# Adafruit_QT_Py_RP2040.net
KiCad netlist of a schematic drawn in EAGLE
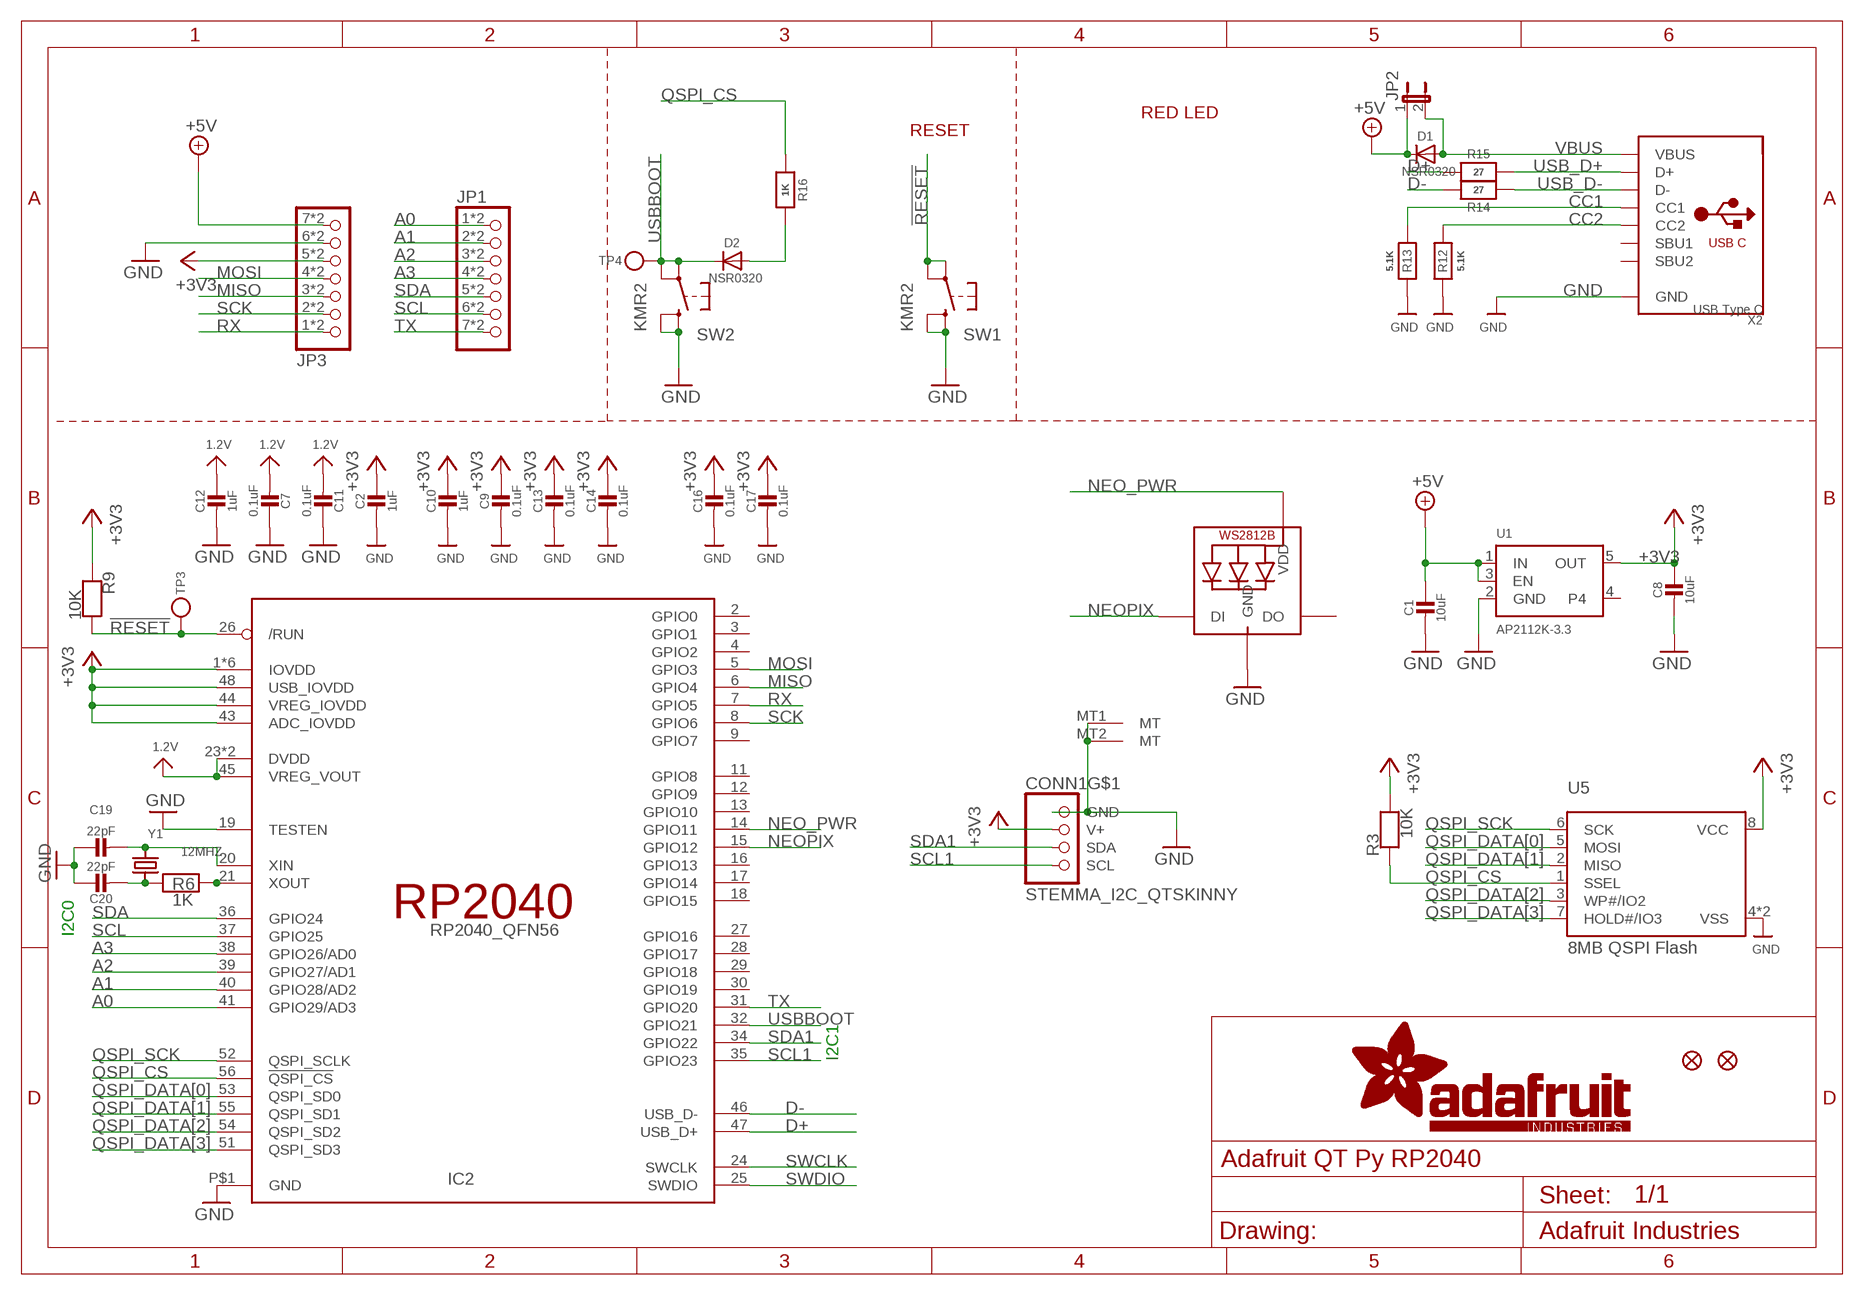
[diagram p0: schematic, sheet 1]

(export (version "E")
  (design (tool "Eeschema 10.0.6"))
  (components
    (comp (ref "C1")
      (value "10uF")
      (footprint "eagle-import:0805-NO")
      (libsource (lib "eagle-import") (part "CAP_CERAMIC0805-NOOUTLINE"))
    )
    (comp (ref "C2")
      (value "1uF")
      (footprint "eagle-import:0603-NO")
      (libsource (lib "eagle-import") (part "CAP_CERAMIC0603_NO"))
    )
    (comp (ref "C7")
      (value "0.1uF")
      (footprint "eagle-import:_0402NO")
      (libsource (lib "eagle-import") (part "CAP_CERAMIC_0402NO"))
    )
    (comp (ref "C8")
      (value "10uF")
      (footprint "eagle-import:0805-NO")
      (libsource (lib "eagle-import") (part "CAP_CERAMIC0805-NOOUTLINE"))
    )
    (comp (ref "C9")
      (value "0.1uF")
      (footprint "eagle-import:_0402NO")
      (libsource (lib "eagle-import") (part "CAP_CERAMIC_0402NO"))
    )
    (comp (ref "C10")
      (value "1uF")
      (footprint "eagle-import:0603-NO")
      (libsource (lib "eagle-import") (part "CAP_CERAMIC0603_NO"))
    )
    (comp (ref "C11")
      (value "0.1uF")
      (footprint "eagle-import:_0402NO")
      (libsource (lib "eagle-import") (part "CAP_CERAMIC_0402NO"))
    )
    (comp (ref "C12")
      (value "1uF")
      (footprint "eagle-import:0603-NO")
      (libsource (lib "eagle-import") (part "CAP_CERAMIC0603_NO"))
    )
    (comp (ref "C13")
      (value "0.1uF")
      (footprint "eagle-import:_0402NO")
      (libsource (lib "eagle-import") (part "CAP_CERAMIC_0402NO"))
    )
    (comp (ref "C14")
      (value "0.1uF")
      (footprint "eagle-import:_0402NO")
      (libsource (lib "eagle-import") (part "CAP_CERAMIC_0402NO"))
    )
    (comp (ref "C16")
      (value "0.1uF")
      (footprint "eagle-import:_0402NO")
      (libsource (lib "eagle-import") (part "CAP_CERAMIC_0402NO"))
    )
    (comp (ref "C17")
      (value "0.1uF")
      (footprint "eagle-import:_0402NO")
      (libsource (lib "eagle-import") (part "CAP_CERAMIC_0402NO"))
    )
    (comp (ref "C19")
      (value "22pF")
      (footprint "eagle-import:_0402NO")
      (libsource (lib "eagle-import") (part "CAP_CERAMIC_0402NO"))
    )
    (comp (ref "C20")
      (value "22pF")
      (footprint "eagle-import:_0402NO")
      (libsource (lib "eagle-import") (part "CAP_CERAMIC_0402NO"))
    )
    (comp (ref "CONN1")
      (value "STEMMA_I2C_QTSKINNY")
      (footprint "eagle-import:JST_SH4_SKINNY")
      (libsource (lib "eagle-import") (part "STEMMA_I2C_QTSKINNY"))
    )
    (comp (ref "D1")
      (value "NSR0320")
      (footprint "eagle-import:SOD-323_MINI")
      (libsource (lib "eagle-import") (part "DIODE_SOD323MINI"))
    )
    (comp (ref "D2")
      (value "NSR0320")
      (footprint "eagle-import:SOD-323_MINI")
      (libsource (lib "eagle-import") (part "DIODE_SOD323MINI"))
    )
    (comp (ref "IC2")
      (value "RP2040_QFN56")
      (footprint "eagle-import:QFN56_7MM_REDUCEDEPAD")
      (libsource (lib "eagle-import") (part "RP2040_QFN56"))
    )
    (comp (ref "JP1")
      (value "HEADER-1X7_CASTEL")
      (footprint "eagle-import:1X07_CASTEL")
      (libsource (lib "eagle-import") (part "HEADER-1X7_CASTEL"))
    )
    (comp (ref "JP2")
      (value "JUMPER-2SMD-NO")
      (footprint "eagle-import:SJ_2S-NO")
      (libsource (lib "eagle-import") (part "JUMPER-2SMD-NO"))
    )
    (comp (ref "JP3")
      (value "HEADER-1X7_CASTEL")
      (footprint "eagle-import:1X07_CASTEL")
      (libsource (lib "eagle-import") (part "HEADER-1X7_CASTEL"))
    )
    (comp (ref "LED1")
      (value "WS2812B_SK6805_1515")
      (footprint "eagle-import:SK6805_1515")
      (libsource (lib "eagle-import") (part "WS2812B_SK6805_1515"))
    )
    (comp (ref "R3")
      (value "10K")
      (footprint "eagle-import:_0402NO")
      (libsource (lib "eagle-import") (part "RESISTOR_0402NO"))
    )
    (comp (ref "R6")
      (value "1K")
      (footprint "eagle-import:_0402NO")
      (libsource (lib "eagle-import") (part "RESISTOR_0402NO"))
    )
    (comp (ref "R9")
      (value "10K")
      (footprint "eagle-import:_0402NO")
      (libsource (lib "eagle-import") (part "RESISTOR_0402NO"))
    )
    (comp (ref "R12")
      (value "5.1K")
      (footprint "eagle-import:_0402NO")
      (libsource (lib "eagle-import") (part "RESISTOR_0402NO"))
    )
    (comp (ref "R13")
      (value "5.1K")
      (footprint "eagle-import:_0402NO")
      (libsource (lib "eagle-import") (part "RESISTOR_0402NO"))
    )
    (comp (ref "R14")
      (value "27")
      (footprint "eagle-import:_0402NO")
      (libsource (lib "eagle-import") (part "RESISTOR_0402NO"))
    )
    (comp (ref "R15")
      (value "27")
      (footprint "eagle-import:_0402NO")
      (libsource (lib "eagle-import") (part "RESISTOR_0402NO"))
    )
    (comp (ref "R16")
      (value "1K")
      (footprint "eagle-import:_0402NO")
      (libsource (lib "eagle-import") (part "RESISTOR_0402NO"))
    )
    (comp (ref "SW1")
      (value "KMR2")
      (footprint "eagle-import:BTN_KMR2_4.6X2.8")
      (libsource (lib "eagle-import") (part "SWITCH_TACT_SMT4.6X2.8"))
    )
    (comp (ref "SW2")
      (value "KMR2")
      (footprint "eagle-import:BTN_KMR2_4.6X2.8")
      (libsource (lib "eagle-import") (part "SWITCH_TACT_SMT4.6X2.8"))
    )
    (comp (ref "TP3")
      (value "TESTPOINTROUND1.5MMNO")
      (footprint "eagle-import:TESTPOINT_ROUND_1.5MM_NO")
      (libsource (lib "eagle-import") (part "TESTPOINTROUND1.5MMNO"))
    )
    (comp (ref "TP4")
      (value "TESTPOINTROUND1.5MMNO")
      (footprint "eagle-import:TESTPOINT_ROUND_1.5MM_NO")
      (libsource (lib "eagle-import") (part "TESTPOINTROUND1.5MMNO"))
    )
    (comp (ref "U$6")
      (value "FIDUCIAL_1MM")
      (footprint "eagle-import:FIDUCIAL_1MM")
      (libsource (lib "eagle-import") (part "FIDUCIAL_1MM"))
    )
    (comp (ref "U$8")
      (value "FIDUCIAL_1MM")
      (footprint "eagle-import:FIDUCIAL_1MM")
      (libsource (lib "eagle-import") (part "FIDUCIAL_1MM"))
    )
    (comp (ref "U1")
      (value "AP2112K-3.3")
      (footprint "eagle-import:SOT23-5")
      (libsource (lib "eagle-import") (part "VREG_SOT23-5"))
    )
    (comp (ref "U5")
      (value "8MB QSPI Flash")
      (footprint "eagle-import:USON8_4X4")
      (libsource (lib "eagle-import") (part "SPIFLASH_8PIN_4X4"))
    )
    (comp (ref "X2")
      (value "USB Type C")
      (footprint "eagle-import:USB_C_CUSB31-CFM2AX-01-X")
      (libsource (lib "eagle-import") (part "USB_C"))
    )
    (comp (ref "Y1")
      (value "12MHZ")
      (footprint "eagle-import:CRYSTAL_2.5X2")
      (libsource (lib "eagle-import") (part "CRYSTAL2.5X2.0"))
    )
  )
  (nets
    (net (code "1") (name "+3V3") (class "Default")
      (node (ref "C10") (pin "1") (pinfunction "1_1") (pintype "passive"))
      (node (ref "C13") (pin "1") (pinfunction "1_1") (pintype "passive"))
      (node (ref "C14") (pin "1") (pinfunction "1_1") (pintype "passive"))
      (node (ref "C16") (pin "1") (pinfunction "1_1") (pintype "passive"))
      (node (ref "C17") (pin "1") (pinfunction "1_1") (pintype "passive"))
      (node (ref "C2") (pin "1") (pinfunction "1_1") (pintype "passive"))
      (node (ref "C8") (pin "1") (pinfunction "1_1") (pintype "passive"))
      (node (ref "C9") (pin "1") (pinfunction "1_1") (pintype "passive"))
      (node (ref "CONN1") (pin "2") (pinfunction "V+_2") (pintype "passive"))
      (node (ref "IC2") (pin "1") (pinfunction "IOVDD_1") (pintype "power_in"))
      (node (ref "IC2") (pin "10") (pinfunction "IOVDD_10") (pintype "power_in"))
      (node (ref "IC2") (pin "22") (pinfunction "IOVDD_22") (pintype "power_in"))
      (node (ref "IC2") (pin "33") (pinfunction "IOVDD_33") (pintype "power_in"))
      (node (ref "IC2") (pin "42") (pinfunction "IOVDD_42") (pintype "power_in"))
      (node (ref "IC2") (pin "43") (pinfunction "ADC_IOVDD_43") (pintype "power_in"))
      (node (ref "IC2") (pin "44") (pinfunction "VREG_IOVDD_44") (pintype "power_in"))
      (node (ref "IC2") (pin "48") (pinfunction "USB_IOVDD_48") (pintype "power_in"))
      (node (ref "IC2") (pin "49") (pinfunction "IOVDD_49") (pintype "power_in"))
      (node (ref "JP3") (pin "5") (pinfunction "5_5") (pintype "passive"))
      (node (ref "JP3") (pin "5C") (pinfunction "5_5C") (pintype "passive"))
      (node (ref "R3") (pin "2") (pinfunction "2_2") (pintype "passive"))
      (node (ref "R9") (pin "1") (pinfunction "1_1") (pintype "passive"))
      (node (ref "U1") (pin "5") (pinfunction "OUT_5") (pintype "power_in"))
      (node (ref "U5") (pin "8") (pinfunction "VCC_8") (pintype "bidirectional"))
    )
    (net (code "2") (name "+5V") (class "Default")
      (node (ref "C1") (pin "1") (pinfunction "1_1") (pintype "passive"))
      (node (ref "D1") (pin "C") (pinfunction "C_C") (pintype "passive"))
      (node (ref "JP2") (pin "1") (pinfunction "1_1") (pintype "passive"))
      (node (ref "JP3") (pin "7") (pinfunction "7_7") (pintype "passive"))
      (node (ref "JP3") (pin "7C") (pinfunction "7_7C") (pintype "passive"))
      (node (ref "U1") (pin "1") (pinfunction "IN_1") (pintype "power_in"))
      (node (ref "U1") (pin "3") (pinfunction "EN_3") (pintype "input"))
    )
    (net (code "3") (name "/A0") (class "Default")
      (node (ref "IC2") (pin "41") (pinfunction "GPIO29/AD3_41") (pintype "bidirectional"))
      (node (ref "JP1") (pin "1") (pinfunction "1_1") (pintype "passive"))
      (node (ref "JP1") (pin "1C") (pinfunction "1_1C") (pintype "passive"))
    )
    (net (code "4") (name "/A1") (class "Default")
      (node (ref "IC2") (pin "40") (pinfunction "GPIO28/AD2_40") (pintype "bidirectional"))
      (node (ref "JP1") (pin "2") (pinfunction "2_2") (pintype "passive"))
      (node (ref "JP1") (pin "2C") (pinfunction "2_2C") (pintype "passive"))
    )
    (net (code "5") (name "/A2") (class "Default")
      (node (ref "IC2") (pin "39") (pinfunction "GPIO27/AD1_39") (pintype "bidirectional"))
      (node (ref "JP1") (pin "3") (pinfunction "3_3") (pintype "passive"))
      (node (ref "JP1") (pin "3C") (pinfunction "3_3C") (pintype "passive"))
    )
    (net (code "6") (name "/A3") (class "Default")
      (node (ref "IC2") (pin "38") (pinfunction "GPIO26/AD0_38") (pintype "bidirectional"))
      (node (ref "JP1") (pin "4") (pinfunction "4_4") (pintype "passive"))
      (node (ref "JP1") (pin "4C") (pinfunction "4_4C") (pintype "passive"))
    )
    (net (code "7") (name "/CC1") (class "Default")
      (node (ref "R13") (pin "2") (pinfunction "2_2") (pintype "passive"))
      (node (ref "X2") (pin "A5") (pinfunction "CC1_A5") (pintype "bidirectional"))
    )
    (net (code "8") (name "/CC2") (class "Default")
      (node (ref "R12") (pin "2") (pinfunction "2_2") (pintype "passive"))
      (node (ref "X2") (pin "B5") (pinfunction "CC2_B5") (pintype "bidirectional"))
    )
    (net (code "9") (name "/D+") (class "Default")
      (node (ref "IC2") (pin "47") (pinfunction "USB_D+_47") (pintype "bidirectional"))
      (node (ref "R15") (pin "2") (pinfunction "2_2") (pintype "passive"))
    )
    (net (code "10") (name "/D-") (class "Default")
      (node (ref "IC2") (pin "46") (pinfunction "USB_D-_46") (pintype "bidirectional"))
      (node (ref "R14") (pin "2") (pinfunction "2_2") (pintype "passive"))
    )
    (net (code "11") (name "/MISO") (class "Default")
      (node (ref "IC2") (pin "6") (pinfunction "GPIO4_6") (pintype "bidirectional"))
      (node (ref "JP3") (pin "3") (pinfunction "3_3") (pintype "passive"))
      (node (ref "JP3") (pin "3C") (pinfunction "3_3C") (pintype "passive"))
    )
    (net (code "12") (name "/MOSI") (class "Default")
      (node (ref "IC2") (pin "5") (pinfunction "GPIO3_5") (pintype "bidirectional"))
      (node (ref "JP3") (pin "4") (pinfunction "4_4") (pintype "passive"))
      (node (ref "JP3") (pin "4C") (pinfunction "4_4C") (pintype "passive"))
    )
    (net (code "13") (name "/NEOPIX") (class "Default")
      (node (ref "IC2") (pin "15") (pinfunction "GPIO12_15") (pintype "bidirectional"))
      (node (ref "LED1") (pin "1") (pinfunction "DI_1") (pintype "input"))
    )
    (net (code "14") (name "/NEO_PWR") (class "Default")
      (node (ref "IC2") (pin "14") (pinfunction "GPIO11_14") (pintype "bidirectional"))
      (node (ref "LED1") (pin "2") (pinfunction "VDD_2") (pintype "power_in"))
    )
    (net (code "15") (name "/QSPI_CS") (class "Default")
      (node (ref "IC2") (pin "56") (pinfunction "~{QSPI_CS}_56") (pintype "bidirectional"))
      (node (ref "R16") (pin "1") (pinfunction "1_1") (pintype "passive"))
      (node (ref "R3") (pin "1") (pinfunction "1_1") (pintype "passive"))
      (node (ref "U5") (pin "1") (pinfunction "SSEL_1") (pintype "bidirectional"))
    )
    (net (code "16") (name "/QSPI_DATA[0]") (class "Default")
      (node (ref "IC2") (pin "53") (pinfunction "QSPI_SD0_53") (pintype "bidirectional"))
      (node (ref "U5") (pin "5") (pinfunction "MOSI_5") (pintype "bidirectional"))
    )
    (net (code "17") (name "/QSPI_DATA[1]") (class "Default")
      (node (ref "IC2") (pin "55") (pinfunction "QSPI_SD1_55") (pintype "bidirectional"))
      (node (ref "U5") (pin "2") (pinfunction "MISO_2") (pintype "bidirectional"))
    )
    (net (code "18") (name "/QSPI_DATA[2]") (class "Default")
      (node (ref "IC2") (pin "54") (pinfunction "QSPI_SD2_54") (pintype "bidirectional"))
      (node (ref "U5") (pin "3") (pinfunction "WP#/IO2_3") (pintype "bidirectional"))
    )
    (net (code "19") (name "/QSPI_DATA[3]") (class "Default")
      (node (ref "IC2") (pin "51") (pinfunction "QSPI_SD3_51") (pintype "bidirectional"))
      (node (ref "U5") (pin "7") (pinfunction "HOLD#/IO3_7") (pintype "bidirectional"))
    )
    (net (code "20") (name "/QSPI_SCK") (class "Default")
      (node (ref "IC2") (pin "52") (pinfunction "QSPI_SCLK_52") (pintype "bidirectional"))
      (node (ref "U5") (pin "6") (pinfunction "SCK_6") (pintype "bidirectional"))
    )
    (net (code "21") (name "/RX") (class "Default")
      (node (ref "IC2") (pin "7") (pinfunction "GPIO5_7") (pintype "bidirectional"))
      (node (ref "JP3") (pin "1") (pinfunction "1_1") (pintype "passive"))
      (node (ref "JP3") (pin "1C") (pinfunction "1_1C") (pintype "passive"))
    )
    (net (code "22") (name "/SCK") (class "Default")
      (node (ref "IC2") (pin "8") (pinfunction "GPIO6_8") (pintype "bidirectional"))
      (node (ref "JP3") (pin "2") (pinfunction "2_2") (pintype "passive"))
      (node (ref "JP3") (pin "2C") (pinfunction "2_2C") (pintype "passive"))
    )
    (net (code "23") (name "/SCL") (class "Default")
      (node (ref "IC2") (pin "37") (pinfunction "GPIO25_37") (pintype "bidirectional"))
      (node (ref "JP1") (pin "6") (pinfunction "6_6") (pintype "passive"))
      (node (ref "JP1") (pin "6C") (pinfunction "6_6C") (pintype "passive"))
    )
    (net (code "24") (name "/SCL1") (class "Default")
      (node (ref "CONN1") (pin "4") (pinfunction "SCL_4") (pintype "passive"))
      (node (ref "IC2") (pin "35") (pinfunction "GPIO23_35") (pintype "bidirectional"))
    )
    (net (code "25") (name "/SDA") (class "Default")
      (node (ref "IC2") (pin "36") (pinfunction "GPIO24_36") (pintype "bidirectional"))
      (node (ref "JP1") (pin "5") (pinfunction "5_5") (pintype "passive"))
      (node (ref "JP1") (pin "5C") (pinfunction "5_5C") (pintype "passive"))
    )
    (net (code "26") (name "/SDA1") (class "Default")
      (node (ref "CONN1") (pin "3") (pinfunction "SDA_3") (pintype "passive"))
      (node (ref "IC2") (pin "34") (pinfunction "GPIO22_34") (pintype "bidirectional"))
    )
    (net (code "27") (name "/SWCLK") (class "Default")
      (node (ref "IC2") (pin "24") (pinfunction "SWCLK_24") (pintype "bidirectional"))
    )
    (net (code "28") (name "/SWDIO") (class "Default")
      (node (ref "IC2") (pin "25") (pinfunction "SWDIO_25") (pintype "bidirectional"))
    )
    (net (code "29") (name "/TX") (class "Default")
      (node (ref "IC2") (pin "31") (pinfunction "GPIO20_31") (pintype "bidirectional"))
      (node (ref "JP1") (pin "7") (pinfunction "7_7") (pintype "passive"))
      (node (ref "JP1") (pin "7C") (pinfunction "7_7C") (pintype "passive"))
    )
    (net (code "30") (name "/USBBOOT") (class "Default")
      (node (ref "D2") (pin "C") (pinfunction "C_C") (pintype "passive"))
      (node (ref "IC2") (pin "32") (pinfunction "GPIO21_32") (pintype "bidirectional"))
      (node (ref "SW2") (pin "A") (pinfunction "P_A") (pintype "passive"))
      (node (ref "SW2") (pin "A'") (pinfunction "P1_A'") (pintype "passive"))
      (node (ref "TP4") (pin "P$1") (pinfunction "P$1_P$1") (pintype "bidirectional"))
    )
    (net (code "31") (name "/USB_D+") (class "Default")
      (node (ref "R15") (pin "1") (pinfunction "1_1") (pintype "passive"))
      (node (ref "X2") (pin "A6") (pinfunction "D+_A6") (pintype "bidirectional"))
      (node (ref "X2") (pin "B6") (pinfunction "D+_B6") (pintype "bidirectional"))
    )
    (net (code "32") (name "/USB_D-") (class "Default")
      (node (ref "R14") (pin "1") (pinfunction "1_1") (pintype "passive"))
      (node (ref "X2") (pin "A7") (pinfunction "D-_A7") (pintype "bidirectional"))
      (node (ref "X2") (pin "B7") (pinfunction "D-_B7") (pintype "bidirectional"))
    )
    (net (code "33") (name "/VBUS") (class "Default")
      (node (ref "D1") (pin "A") (pinfunction "A_A") (pintype "passive"))
      (node (ref "JP2") (pin "2") (pinfunction "2_2") (pintype "passive"))
      (node (ref "X2") (pin "A4B9") (pinfunction "VBUS_A4B9") (pintype "power_in"))
      (node (ref "X2") (pin "B4A9") (pinfunction "VBUS_B4A9") (pintype "power_in"))
    )
    (net (code "34") (name "/~{RESET}") (class "Default")
      (node (ref "IC2") (pin "26") (pinfunction "/RUN_26") (pintype "bidirectional"))
      (node (ref "R9") (pin "2") (pinfunction "2_2") (pintype "passive"))
      (node (ref "SW1") (pin "A") (pinfunction "P_A") (pintype "passive"))
      (node (ref "SW1") (pin "A'") (pinfunction "P1_A'") (pintype "passive"))
      (node (ref "TP3") (pin "P$1") (pinfunction "P$1_P$1") (pintype "bidirectional"))
    )
    (net (code "35") (name "1.2V") (class "Default")
      (node (ref "C11") (pin "2") (pinfunction "2_2") (pintype "passive"))
      (node (ref "C12") (pin "1") (pinfunction "1_1") (pintype "passive"))
      (node (ref "C7") (pin "2") (pinfunction "2_2") (pintype "passive"))
      (node (ref "IC2") (pin "23") (pinfunction "DVDD_23") (pintype "power_in"))
      (node (ref "IC2") (pin "45") (pinfunction "VREG_VOUT_45") (pintype "power_in"))
      (node (ref "IC2") (pin "50") (pinfunction "DVDD_50") (pintype "power_in"))
    )
    (net (code "36") (name "GND") (class "Default")
      (node (ref "C1") (pin "2") (pinfunction "2_2") (pintype "passive"))
      (node (ref "C10") (pin "2") (pinfunction "2_2") (pintype "passive"))
      (node (ref "C11") (pin "1") (pinfunction "1_1") (pintype "passive"))
      (node (ref "C12") (pin "2") (pinfunction "2_2") (pintype "passive"))
      (node (ref "C13") (pin "2") (pinfunction "2_2") (pintype "passive"))
      (node (ref "C14") (pin "2") (pinfunction "2_2") (pintype "passive"))
      (node (ref "C16") (pin "2") (pinfunction "2_2") (pintype "passive"))
      (node (ref "C17") (pin "2") (pinfunction "2_2") (pintype "passive"))
      (node (ref "C19") (pin "1") (pinfunction "1_1") (pintype "passive"))
      (node (ref "C2") (pin "2") (pinfunction "2_2") (pintype "passive"))
      (node (ref "C20") (pin "1") (pinfunction "1_1") (pintype "passive"))
      (node (ref "C7") (pin "1") (pinfunction "1_1") (pintype "passive"))
      (node (ref "C8") (pin "2") (pinfunction "2_2") (pintype "passive"))
      (node (ref "C9") (pin "2") (pinfunction "2_2") (pintype "passive"))
      (node (ref "CONN1") (pin "1") (pinfunction "GND_1") (pintype "passive"))
      (node (ref "CONN1") (pin "MT1") (pinfunction "MT_MT1") (pintype "bidirectional"))
      (node (ref "CONN1") (pin "MT2") (pinfunction "MT_MT2") (pintype "bidirectional"))
      (node (ref "IC2") (pin "19") (pinfunction "TESTEN_19") (pintype "input"))
      (node (ref "IC2") (pin "P$1") (pinfunction "GND_P$1") (pintype "power_in"))
      (node (ref "JP3") (pin "6") (pinfunction "6_6") (pintype "passive"))
      (node (ref "JP3") (pin "6C") (pinfunction "6_6C") (pintype "passive"))
      (node (ref "LED1") (pin "4") (pinfunction "GND_4") (pintype "power_in"))
      (node (ref "R12") (pin "1") (pinfunction "1_1") (pintype "passive"))
      (node (ref "R13") (pin "1") (pinfunction "1_1") (pintype "passive"))
      (node (ref "SW1") (pin "B") (pinfunction "S_B") (pintype "passive"))
      (node (ref "SW1") (pin "B'") (pinfunction "S1_B'") (pintype "passive"))
      (node (ref "SW2") (pin "B") (pinfunction "S_B") (pintype "passive"))
      (node (ref "SW2") (pin "B'") (pinfunction "S1_B'") (pintype "passive"))
      (node (ref "U1") (pin "2") (pinfunction "GND_2") (pintype "power_in"))
      (node (ref "U5") (pin "4") (pinfunction "VSS_4") (pintype "bidirectional"))
      (node (ref "U5") (pin "PAD") (pinfunction "VSS_PAD") (pintype "bidirectional"))
      (node (ref "X2") (pin "A1B12") (pinfunction "GND_A1B12") (pintype "power_in"))
      (node (ref "X2") (pin "B1A12") (pinfunction "GND_B1A12") (pintype "power_in"))
    )
    (net (code "37") (name "Net-(C20-Pad2)") (class "Default")
      (node (ref "C20") (pin "2") (pinfunction "2_2") (pintype "passive"))
      (node (ref "R6") (pin "1") (pinfunction "1_1") (pintype "passive"))
      (node (ref "Y1") (pin "1") (pinfunction "1_1") (pintype "passive"))
    )
    (net (code "38") (name "Net-(D2-PadA)") (class "Default")
      (node (ref "D2") (pin "A") (pinfunction "A_A") (pintype "passive"))
      (node (ref "R16") (pin "2") (pinfunction "2_2") (pintype "passive"))
    )
    (net (code "39") (name "Net-(IC2-XIN)") (class "Default")
      (node (ref "C19") (pin "2") (pinfunction "2_2") (pintype "passive"))
      (node (ref "IC2") (pin "20") (pinfunction "XIN_20") (pintype "input"))
      (node (ref "Y1") (pin "3") (pinfunction "2_3") (pintype "passive"))
    )
    (net (code "40") (name "Net-(IC2-XOUT)") (class "Default")
      (node (ref "IC2") (pin "21") (pinfunction "XOUT_21") (pintype "output"))
      (node (ref "R6") (pin "2") (pinfunction "2_2") (pintype "passive"))
    )
    (net (code "41") (name "unconnected-(IC2-GPIO0-Pad2)") (class "Default")
      (node (ref "IC2") (pin "2") (pinfunction "GPIO0_2") (pintype "bidirectional"))
    )
    (net (code "42") (name "unconnected-(IC2-GPIO1-Pad3)") (class "Default")
      (node (ref "IC2") (pin "3") (pinfunction "GPIO1_3") (pintype "bidirectional"))
    )
    (net (code "43") (name "unconnected-(IC2-GPIO2-Pad4)") (class "Default")
      (node (ref "IC2") (pin "4") (pinfunction "GPIO2_4") (pintype "bidirectional"))
    )
    (net (code "44") (name "unconnected-(IC2-GPIO7-Pad9)") (class "Default")
      (node (ref "IC2") (pin "9") (pinfunction "GPIO7_9") (pintype "bidirectional"))
    )
    (net (code "45") (name "unconnected-(IC2-GPIO8-Pad11)") (class "Default")
      (node (ref "IC2") (pin "11") (pinfunction "GPIO8_11") (pintype "bidirectional"))
    )
    (net (code "46") (name "unconnected-(IC2-GPIO9-Pad12)") (class "Default")
      (node (ref "IC2") (pin "12") (pinfunction "GPIO9_12") (pintype "bidirectional"))
    )
    (net (code "47") (name "unconnected-(IC2-GPIO10-Pad13)") (class "Default")
      (node (ref "IC2") (pin "13") (pinfunction "GPIO10_13") (pintype "bidirectional"))
    )
    (net (code "48") (name "unconnected-(IC2-GPIO13-Pad16)") (class "Default")
      (node (ref "IC2") (pin "16") (pinfunction "GPIO13_16") (pintype "bidirectional"))
    )
    (net (code "49") (name "unconnected-(IC2-GPIO14-Pad17)") (class "Default")
      (node (ref "IC2") (pin "17") (pinfunction "GPIO14_17") (pintype "bidirectional"))
    )
    (net (code "50") (name "unconnected-(IC2-GPIO15-Pad18)") (class "Default")
      (node (ref "IC2") (pin "18") (pinfunction "GPIO15_18") (pintype "bidirectional"))
    )
    (net (code "51") (name "unconnected-(IC2-GPIO16-Pad27)") (class "Default")
      (node (ref "IC2") (pin "27") (pinfunction "GPIO16_27") (pintype "bidirectional"))
    )
    (net (code "52") (name "unconnected-(IC2-GPIO17-Pad28)") (class "Default")
      (node (ref "IC2") (pin "28") (pinfunction "GPIO17_28") (pintype "bidirectional"))
    )
    (net (code "53") (name "unconnected-(IC2-GPIO18-Pad29)") (class "Default")
      (node (ref "IC2") (pin "29") (pinfunction "GPIO18_29") (pintype "bidirectional"))
    )
    (net (code "54") (name "unconnected-(IC2-GPIO19-Pad30)") (class "Default")
      (node (ref "IC2") (pin "30") (pinfunction "GPIO19_30") (pintype "bidirectional"))
    )
    (net (code "55") (name "unconnected-(LED1-DO-Pad3)") (class "Default")
      (node (ref "LED1") (pin "3") (pinfunction "DO_3") (pintype "output"))
    )
    (net (code "56") (name "unconnected-(U1-P4-Pad4)") (class "Default")
      (node (ref "U1") (pin "4") (pinfunction "P4_4") (pintype "bidirectional"))
    )
    (net (code "57") (name "unconnected-(X2-SBU1-PadA8)") (class "Default")
      (node (ref "X2") (pin "A8") (pinfunction "SBU1_A8") (pintype "bidirectional"))
    )
    (net (code "58") (name "unconnected-(X2-SBU2-PadB8)") (class "Default")
      (node (ref "X2") (pin "B8") (pinfunction "SBU2_B8") (pintype "bidirectional"))
    )
  )
)
